# WirelessConnectivity.net
KiCad netlist of a schematic drawn in Altium Designer
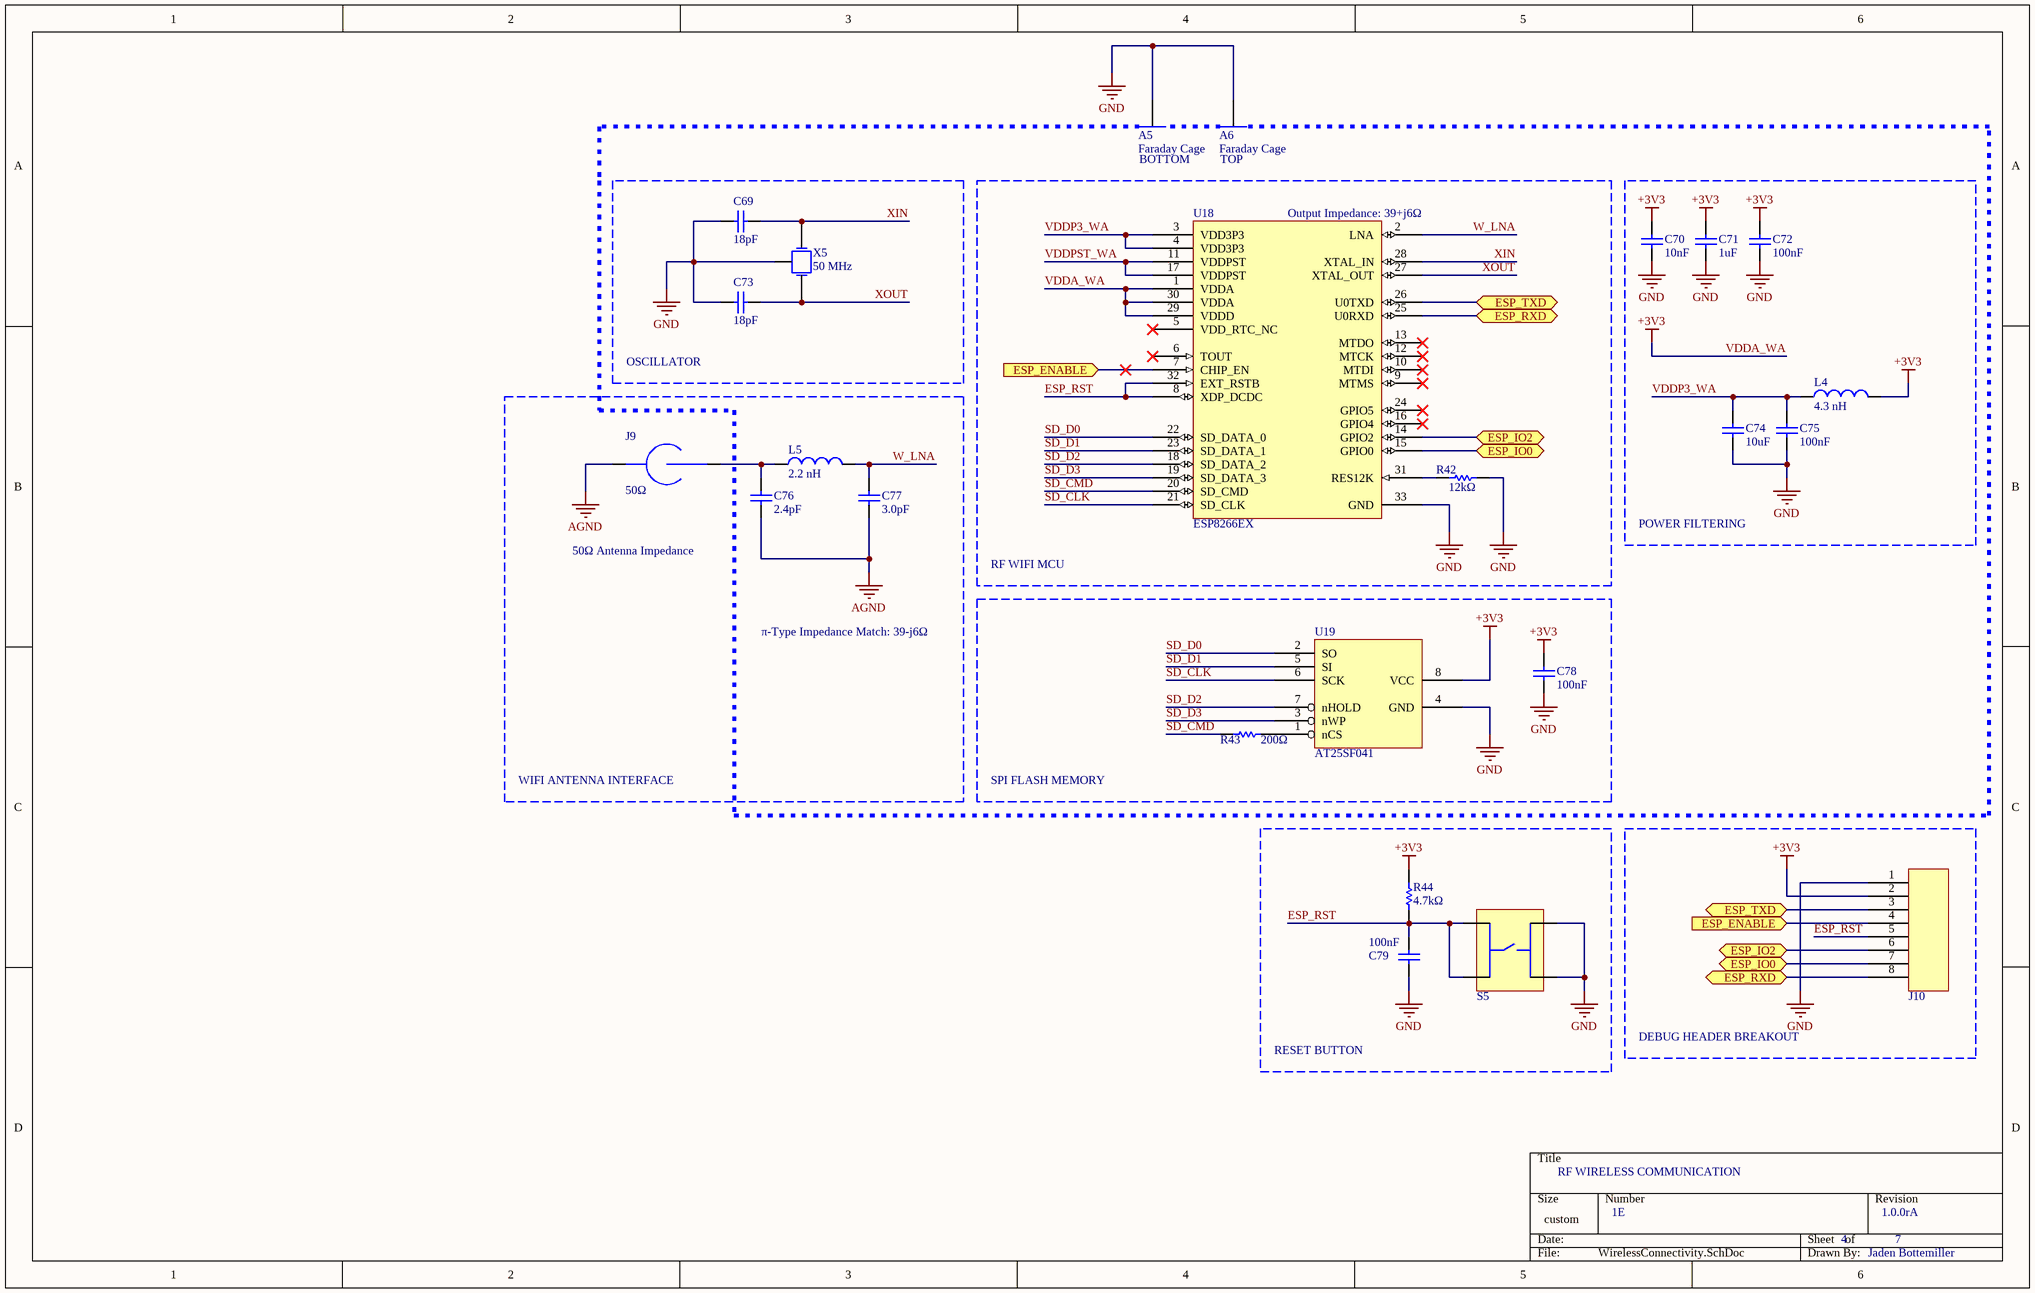
[diagram p0: WirelessConnectivity.SchDoc]

(export (version "E")
  (design (tool "Eeschema 10.0.6"))
  (components
    (comp (ref "A5")
      (value "Faraday Cage")
      (description "Standard Faraday Cage")
      (libsource (lib "NikoboticsLib") (part "Faraday Cage"))
    )
    (comp (ref "A6")
      (value "Faraday Cage")
      (description "Standard Faraday Cage")
      (libsource (lib "NikoboticsLib") (part "Faraday Cage"))
    )
    (comp (ref "C69")
      (value "18pF")
      (description "Standard Capacitor")
      (fields (field (name "Comment") "CAP"))
      (libsource (lib "NikoboticsLib") (part "CAP"))
    )
    (comp (ref "C70")
      (value "10nF")
      (description "Standard Capacitor")
      (fields (field (name "Comment") "CAP"))
      (libsource (lib "NikoboticsLib") (part "CAP"))
    )
    (comp (ref "C71")
      (value "1uF")
      (description "Standard Capacitor")
      (fields (field (name "Comment") "CAP"))
      (libsource (lib "NikoboticsLib") (part "CAP"))
    )
    (comp (ref "C72")
      (value "100nF")
      (description "Standard Capacitor")
      (fields (field (name "Comment") "CAP"))
      (libsource (lib "NikoboticsLib") (part "CAP"))
    )
    (comp (ref "C73")
      (value "18pF")
      (description "Standard Capacitor")
      (fields (field (name "Comment") "CAP"))
      (libsource (lib "NikoboticsLib") (part "CAP"))
    )
    (comp (ref "C74")
      (value "10uF")
      (description "Standard Capacitor")
      (fields (field (name "Comment") "CAP"))
      (libsource (lib "NikoboticsLib") (part "CAP"))
    )
    (comp (ref "C75")
      (value "100nF")
      (description "Standard Capacitor")
      (fields (field (name "Comment") "CAP"))
      (libsource (lib "NikoboticsLib") (part "CAP"))
    )
    (comp (ref "C76")
      (value "2.4pF")
      (description "Standard Capacitor")
      (fields (field (name "Comment") "CAP"))
      (libsource (lib "NikoboticsLib") (part "CAP"))
    )
    (comp (ref "C77")
      (value "3.0pF")
      (description "Standard Capacitor")
      (fields (field (name "Comment") "CAP"))
      (libsource (lib "NikoboticsLib") (part "CAP"))
    )
    (comp (ref "C78")
      (value "100nF")
      (description "Standard Capacitor")
      (fields (field (name "Comment") "CAP"))
      (libsource (lib "NikoboticsLib") (part "CAP"))
    )
    (comp (ref "C79")
      (value "100nF")
      (description "Standard Capacitor")
      (fields (field (name "Comment") "CAP"))
      (libsource (lib "NikoboticsLib") (part "CAP"))
    )
    (comp (ref "J9")
      (value "Coaxial Connection")
      (description "Coaxial Connection, e.g. to antennae")
      (fields (field (name "IMPEDANCE") "50Ω"))
      (libsource (lib "NikoboticsLib") (part "COAX"))
    )
    (comp (ref "J10")
      (value "8 Pin Connector")
      (description "Standard 8 Pin Connector")
      (libsource (lib "NikoboticsLib") (part "CONN_8PIN"))
    )
    (comp (ref "L4")
      (value "4.3 nH")
      (description "Standard Inductor")
      (fields (field (name "Comment") "IND"))
      (libsource (lib "NikoboticsLib") (part "IND"))
    )
    (comp (ref "L5")
      (value "2.2 nH")
      (description "Standard Inductor")
      (fields (field (name "Comment") "IND"))
      (libsource (lib "NikoboticsLib") (part "IND"))
    )
    (comp (ref "R42")
      (value "12kΩ")
      (description "Standard Resistor")
      (fields (field (name "TOLERANCE") "1%") (field (name "Comment") "RES"))
      (libsource (lib "NikoboticsLib") (part "RES"))
    )
    (comp (ref "R43")
      (value "200Ω")
      (description "Standard Resistor")
      (fields (field (name "Comment") "RES"))
      (libsource (lib "NikoboticsLib") (part "RES"))
    )
    (comp (ref "R44")
      (value "4.7kΩ")
      (description "Standard Resistor")
      (fields (field (name "TOLERANCE") "1%") (field (name "Comment") "RES"))
      (libsource (lib "NikoboticsLib") (part "RES"))
    )
    (comp (ref "S5")
      (value "Pushbutton")
      (description "Standard Pushbutton with 4 Terminals")
      (libsource (lib "NikoboticsLib") (part "PUSHBTN_4T"))
    )
    (comp (ref "U18")
      (value "ESP8266EX")
      (description "IC RF TxRx + MCU WiFi 802.11b/g/n 2.4GHz")
      (libsource (lib "NikoboticsLib") (part "ESP8266EX"))
    )
    (comp (ref "U19")
      (value "AT25SF041")
      (description "FLASH Memory IC 4Mb (512K x 8) SPI 104MHz  8-SOIC")
      (libsource (lib "NikoboticsLib") (part "AT25SF041"))
    )
    (comp (ref "X5")
      (value "50 MHz")
      (description "Standard Crystal Oscillator with a ground connection.")
      (fields (field (name "Comment") "Crystal Oscillator"))
      (libsource (lib "NikoboticsLib") (part "OSC_1GND"))
    )
  )
  (nets
    (net (code "1") (name "+3V3") (class "Default")
      (node (ref "C70") (pin "2") (pinfunction "2_2") (pintype "passive"))
      (node (ref "C71") (pin "2") (pinfunction "2_2") (pintype "passive"))
      (node (ref "C72") (pin "2") (pinfunction "2_2") (pintype "passive"))
      (node (ref "C78") (pin "2") (pinfunction "2_2") (pintype "passive"))
      (node (ref "J10") (pin "2") (pinfunction "Pin_2") (pintype "passive"))
      (node (ref "L4") (pin "2") (pinfunction "2_2") (pintype "passive"))
      (node (ref "R44") (pin "2") (pinfunction "2_2") (pintype "passive"))
      (node (ref "U18") (pin "1") (pinfunction "VDDA_1") (pintype "power_in"))
      (node (ref "U18") (pin "29") (pinfunction "VDDD_29") (pintype "power_in"))
      (node (ref "U18") (pin "30") (pinfunction "VDDA_30") (pintype "power_in"))
      (node (ref "U19") (pin "8") (pinfunction "VCC_8") (pintype "power_in"))
    )
    (net (code "2") (name "/ESP_ENABLE") (class "Default")
      (node (ref "J10") (pin "4") (pinfunction "Pin_4") (pintype "passive"))
      (node (ref "U18") (pin "7") (pinfunction "CHIP_EN_7") (pintype "input"))
    )
    (net (code "3") (name "/ESP_IO0") (class "Default")
      (node (ref "J10") (pin "7") (pinfunction "Pin_7") (pintype "passive"))
      (node (ref "U18") (pin "15") (pinfunction "GPIO0_15") (pintype "bidirectional"))
    )
    (net (code "4") (name "/ESP_IO2") (class "Default")
      (node (ref "J10") (pin "6") (pinfunction "Pin_6") (pintype "passive"))
      (node (ref "U18") (pin "14") (pinfunction "GPIO2_14") (pintype "bidirectional"))
    )
    (net (code "5") (name "/ESP_RST") (class "Default")
      (node (ref "C79") (pin "2") (pinfunction "2_2") (pintype "passive"))
      (node (ref "J10") (pin "5") (pinfunction "Pin_5") (pintype "passive"))
      (node (ref "R44") (pin "1") (pinfunction "1_1") (pintype "passive"))
      (node (ref "S5") (pin "1") (pintype "passive"))
      (node (ref "S5") (pin "2") (pinfunction "Pin_2") (pintype "passive"))
      (node (ref "U18") (pin "32") (pinfunction "EXT_RSTB_32") (pintype "input"))
      (node (ref "U18") (pin "8") (pinfunction "XDP_DCDC_8") (pintype "bidirectional"))
    )
    (net (code "6") (name "/ESP_RXD") (class "Default")
      (node (ref "J10") (pin "8") (pinfunction "Pin_8") (pintype "passive"))
      (node (ref "U18") (pin "25") (pinfunction "U0RXD_25") (pintype "bidirectional"))
    )
    (net (code "7") (name "/ESP_TXD") (class "Default")
      (node (ref "J10") (pin "3") (pinfunction "Pin_3") (pintype "passive"))
      (node (ref "U18") (pin "26") (pinfunction "U0TXD_26") (pintype "bidirectional"))
    )
    (net (code "8") (name "/SD_CLK") (class "Default")
      (node (ref "U18") (pin "21") (pinfunction "SD_CLK_21") (pintype "bidirectional"))
      (node (ref "U19") (pin "6") (pinfunction "SCK_6") (pintype "passive"))
    )
    (net (code "9") (name "/SD_CMD") (class "Default")
      (node (ref "R43") (pin "1") (pinfunction "1_1") (pintype "passive"))
      (node (ref "U18") (pin "20") (pinfunction "SD_CMD_20") (pintype "bidirectional"))
    )
    (net (code "10") (name "/SD_D0") (class "Default")
      (node (ref "U18") (pin "22") (pinfunction "SD_DATA_0_22") (pintype "bidirectional"))
      (node (ref "U19") (pin "2") (pinfunction "SO_2") (pintype "passive"))
    )
    (net (code "11") (name "/SD_D1") (class "Default")
      (node (ref "U18") (pin "23") (pinfunction "SD_DATA_1_23") (pintype "bidirectional"))
      (node (ref "U19") (pin "5") (pinfunction "SI_5") (pintype "passive"))
    )
    (net (code "12") (name "/SD_D2") (class "Default")
      (node (ref "U18") (pin "18") (pinfunction "SD_DATA_2_18") (pintype "bidirectional"))
      (node (ref "U19") (pin "7") (pinfunction "nHOLD_7") (pintype "passive"))
    )
    (net (code "13") (name "/SD_D3") (class "Default")
      (node (ref "U18") (pin "19") (pinfunction "SD_DATA_3_19") (pintype "bidirectional"))
      (node (ref "U19") (pin "3") (pinfunction "nWP_3") (pintype "passive"))
    )
    (net (code "14") (name "/VDDP3_WA") (class "Default")
      (node (ref "C74") (pin "2") (pinfunction "2_2") (pintype "passive"))
      (node (ref "C75") (pin "2") (pinfunction "2_2") (pintype "passive"))
      (node (ref "L4") (pin "1") (pinfunction "1_1") (pintype "passive"))
      (node (ref "U18") (pin "3") (pinfunction "VDD3P3_3") (pintype "power_in"))
      (node (ref "U18") (pin "4") (pinfunction "VDD3P3_4") (pintype "power_in"))
    )
    (net (code "15") (name "/VDDPST_WA") (class "Default")
      (node (ref "U18") (pin "11") (pinfunction "VDDPST_11") (pintype "power_in"))
      (node (ref "U18") (pin "17") (pinfunction "VDDPST_17") (pintype "power_in"))
    )
    (net (code "16") (name "/W_LNA") (class "Default")
      (node (ref "C77") (pin "2") (pinfunction "2_2") (pintype "passive"))
      (node (ref "L5") (pin "2") (pinfunction "2_2") (pintype "passive"))
      (node (ref "U18") (pin "2") (pinfunction "LNA_2") (pintype "bidirectional"))
    )
    (net (code "17") (name "/XIN") (class "Default")
      (node (ref "C69") (pin "1") (pinfunction "1_1") (pintype "passive"))
      (node (ref "U18") (pin "28") (pinfunction "XTAL_IN_28") (pintype "bidirectional"))
      (node (ref "X5") (pin "1") (pinfunction "X1_1") (pintype "passive"))
    )
    (net (code "18") (name "/XOUT") (class "Default")
      (node (ref "C73") (pin "1") (pinfunction "1_1") (pintype "passive"))
      (node (ref "U18") (pin "27") (pinfunction "XTAL_OUT_27") (pintype "bidirectional"))
      (node (ref "X5") (pin "2") (pinfunction "X2_2") (pintype "passive"))
    )
    (net (code "19") (name "AGND") (class "Default")
      (node (ref "C76") (pin "1") (pinfunction "1_1") (pintype "passive"))
      (node (ref "C77") (pin "1") (pinfunction "1_1") (pintype "passive"))
      (node (ref "J9") (pin "2") (pinfunction "2_2") (pintype "passive"))
    )
    (net (code "20") (name "GND") (class "Default")
      (node (ref "A5") (pin "1") (pinfunction "Pin_1") (pintype "passive"))
      (node (ref "A6") (pin "1") (pinfunction "Pin_1") (pintype "passive"))
      (node (ref "C69") (pin "2") (pinfunction "2_2") (pintype "passive"))
      (node (ref "C70") (pin "1") (pinfunction "1_1") (pintype "passive"))
      (node (ref "C71") (pin "1") (pinfunction "1_1") (pintype "passive"))
      (node (ref "C72") (pin "1") (pinfunction "1_1") (pintype "passive"))
      (node (ref "C73") (pin "2") (pinfunction "2_2") (pintype "passive"))
      (node (ref "C74") (pin "1") (pinfunction "1_1") (pintype "passive"))
      (node (ref "C75") (pin "1") (pinfunction "1_1") (pintype "passive"))
      (node (ref "C78") (pin "1") (pinfunction "1_1") (pintype "passive"))
      (node (ref "C79") (pin "1") (pinfunction "1_1") (pintype "passive"))
      (node (ref "J10") (pin "1") (pinfunction "Pin_1") (pintype "passive"))
      (node (ref "R42") (pin "2") (pinfunction "2_2") (pintype "passive"))
      (node (ref "S5") (pin "3") (pinfunction "Pin_3") (pintype "passive"))
      (node (ref "S5") (pin "4") (pinfunction "Pin_4") (pintype "passive"))
      (node (ref "U18") (pin "33") (pinfunction "GND_33") (pintype "power_in"))
      (node (ref "U19") (pin "4") (pinfunction "GND_4") (pintype "power_in"))
      (node (ref "X5") (pin "3") (pinfunction "GND_3") (pintype "passive"))
    )
    (net (code "21") (name "Net-(J9-Pin)") (class "Default")
      (node (ref "C76") (pin "2") (pinfunction "2_2") (pintype "passive"))
      (node (ref "J9") (pin "1") (pinfunction "Pin_1") (pintype "passive"))
      (node (ref "L5") (pin "1") (pinfunction "1_1") (pintype "passive"))
    )
    (net (code "22") (name "Net-(U18-RES12K)") (class "Default")
      (node (ref "R42") (pin "1") (pinfunction "1_1") (pintype "passive"))
      (node (ref "U18") (pin "31") (pinfunction "RES12K_31") (pintype "input"))
    )
    (net (code "23") (name "Net-(U19-nCS)") (class "Default")
      (node (ref "R43") (pin "2") (pinfunction "2_2") (pintype "passive"))
      (node (ref "U19") (pin "1") (pinfunction "nCS_1") (pintype "passive"))
    )
    (net (code "24") (name "unconnected-(U18-GPIO4-Pad16)") (class "Default")
      (node (ref "U18") (pin "16") (pinfunction "GPIO4_16") (pintype "bidirectional+no_connect"))
    )
    (net (code "25") (name "unconnected-(U18-GPIO5-Pad24)") (class "Default")
      (node (ref "U18") (pin "24") (pinfunction "GPIO5_24") (pintype "bidirectional+no_connect"))
    )
    (net (code "26") (name "unconnected-(U18-MTCK-Pad12)") (class "Default")
      (node (ref "U18") (pin "12") (pinfunction "MTCK_12") (pintype "bidirectional+no_connect"))
    )
    (net (code "27") (name "unconnected-(U18-MTDI-Pad10)") (class "Default")
      (node (ref "U18") (pin "10") (pinfunction "MTDI_10") (pintype "bidirectional+no_connect"))
    )
    (net (code "28") (name "unconnected-(U18-MTDO-Pad13)") (class "Default")
      (node (ref "U18") (pin "13") (pinfunction "MTDO_13") (pintype "bidirectional+no_connect"))
    )
    (net (code "29") (name "unconnected-(U18-MTMS-Pad9)") (class "Default")
      (node (ref "U18") (pin "9") (pinfunction "MTMS_9") (pintype "bidirectional+no_connect"))
    )
    (net (code "30") (name "unconnected-(U18-TOUT-Pad6)") (class "Default")
      (node (ref "U18") (pin "6") (pinfunction "TOUT_6") (pintype "input+no_connect"))
    )
    (net (code "31") (name "unconnected-(U18-VDD_RTC_NC-Pad5)") (class "Default")
      (node (ref "U18") (pin "5") (pinfunction "VDD_RTC_NC_5") (pintype "power_in+no_connect"))
    )
  )
)
